# dedica_interface_board.net
KiCad netlist of a schematic drawn in EAGLE
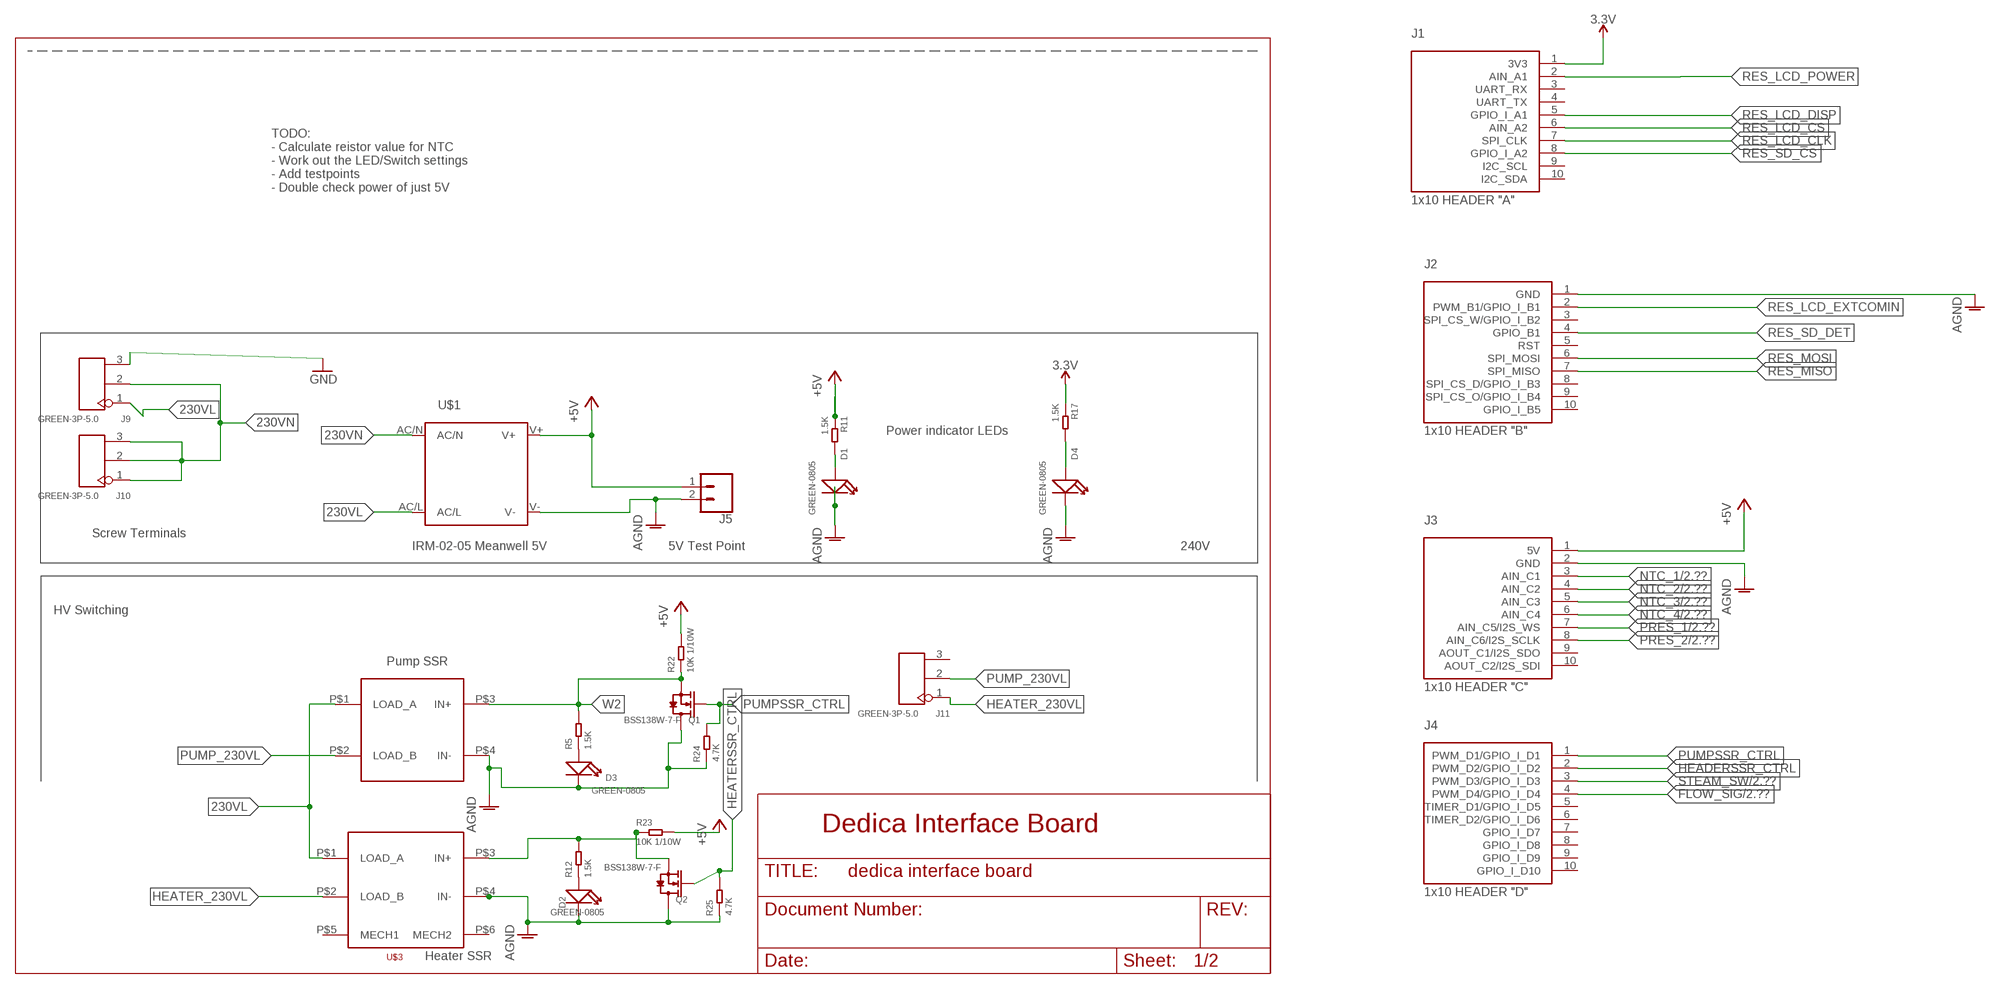
[diagram p0: schematic, sheet 1]
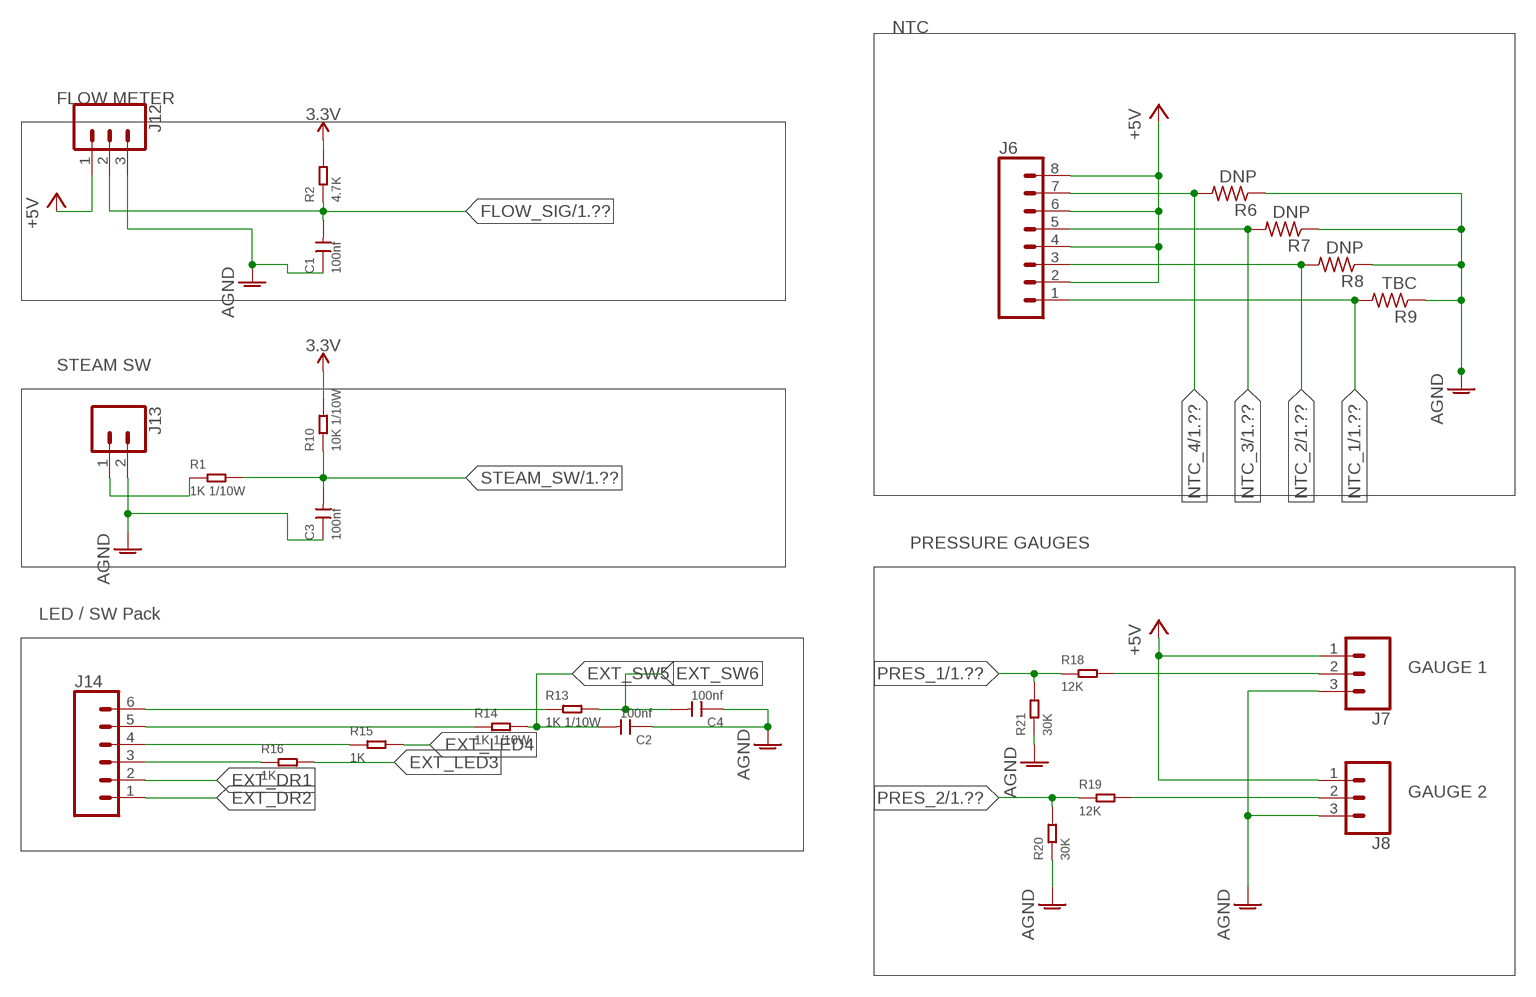
[diagram p1: schematic, sheet 2]

(export (version "E")
  (design (tool "Eeschema 10.0.6"))
  (components
    (comp (ref "C1")
      (value "100nf")
      (footprint "eagle-import:C0603")
      (fields (field (name "MPN") "CC0603KRX7R9BB104"))
      (libsource (lib "eagle-import") (part "CERAMIC-100NF-50V-10%-X7R(0603)"))
    )
    (comp (ref "C2")
      (value "100nf")
      (footprint "eagle-import:C0603")
      (fields (field (name "MPN") "CC0603KRX7R9BB104"))
      (libsource (lib "eagle-import") (part "CERAMIC-100NF-50V-10%-X7R(0603)"))
    )
    (comp (ref "C3")
      (value "100nf")
      (footprint "eagle-import:C0603")
      (fields (field (name "MPN") "CC0603KRX7R9BB104"))
      (libsource (lib "eagle-import") (part "CERAMIC-100NF-50V-10%-X7R(0603)"))
    )
    (comp (ref "C4")
      (value "100nf")
      (footprint "eagle-import:C0603")
      (fields (field (name "MPN") "CC0603KRX7R9BB104"))
      (libsource (lib "eagle-import") (part "CERAMIC-100NF-50V-10%-X7R(0603)"))
    )
    (comp (ref "J6")
      (value "CONN_08\"")
      (footprint "eagle-import:1X08")
      (libsource (lib "eagle-import") (part "CONN_08{dblquote}"))
    )
    (comp (ref "J7")
      (value "CONN_03")
      (footprint "eagle-import:1X03")
      (libsource (lib "eagle-import") (part "CONN_03"))
    )
    (comp (ref "J8")
      (value "CONN_03")
      (footprint "eagle-import:1X03")
      (libsource (lib "eagle-import") (part "CONN_03"))
    )
    (comp (ref "J12")
      (value "CONN_03")
      (footprint "eagle-import:1X03")
      (libsource (lib "eagle-import") (part "CONN_03"))
    )
    (comp (ref "J13")
      (value "CONN_02")
      (footprint "eagle-import:1X02")
      (libsource (lib "eagle-import") (part "CONN_02"))
    )
    (comp (ref "J14")
      (value "CONN_06LOCK")
      (footprint "eagle-import:1X06_LOCK")
      (libsource (lib "eagle-import") (part "CONN_06LOCK"))
    )
    (comp (ref "R1")
      (value "1K 1/10W")
      (footprint "eagle-import:R0603")
      (fields (field (name "MPN") "RC0603JR-071KL"))
      (libsource (lib "eagle-import") (part "SMD-RES-1K-5%-1/10W(0603)"))
    )
    (comp (ref "R2")
      (value "4.7K")
      (footprint "eagle-import:R0603")
      (fields (field (name "MPN") "RC0603JR-074K7L"))
      (libsource (lib "eagle-import") (part "SMD-RES-4.7K-5%-1/10W(0603)"))
    )
    (comp (ref "R6")
      (value "DNP")
      (footprint "eagle-import:R0603")
      (libsource (lib "eagle-import") (part "R-US_R0603"))
    )
    (comp (ref "R7")
      (value "DNP")
      (footprint "eagle-import:R0603")
      (libsource (lib "eagle-import") (part "R-US_R0603"))
    )
    (comp (ref "R8")
      (value "DNP")
      (footprint "eagle-import:R0603")
      (libsource (lib "eagle-import") (part "R-US_R0603"))
    )
    (comp (ref "R9")
      (value "TBC")
      (footprint "eagle-import:R0603")
      (libsource (lib "eagle-import") (part "R-US_R0603"))
    )
    (comp (ref "R10")
      (value "10K 1/10W")
      (footprint "eagle-import:R0603")
      (fields (field (name "MPN") "RC0603JR-0710KL"))
      (libsource (lib "eagle-import") (part "SMD-RES-10K-5%-1/10W(0603)"))
    )
    (comp (ref "R13")
      (value "1K 1/10W")
      (footprint "eagle-import:R0603")
      (fields (field (name "MPN") "RC0603JR-071KL"))
      (libsource (lib "eagle-import") (part "SMD-RES-1K-5%-1/10W(0603)"))
    )
    (comp (ref "R14")
      (value "1K 1/10W")
      (footprint "eagle-import:R0603")
      (fields (field (name "MPN") "RC0603JR-071KL"))
      (libsource (lib "eagle-import") (part "SMD-RES-1K-5%-1/10W(0603)"))
    )
    (comp (ref "R15")
      (value "1K")
      (footprint "eagle-import:R0805")
      (fields (field (name "MPN") "RC0805JR-071KL"))
      (libsource (lib "eagle-import") (part "SMD-RES-330R-5%-1/8W(0805)"))
    )
    (comp (ref "R16")
      (value "1K")
      (footprint "eagle-import:R0805")
      (fields (field (name "MPN") "RC0805JR-071KL"))
      (libsource (lib "eagle-import") (part "SMD-RES-330R-5%-1/8W(0805)"))
    )
    (comp (ref "R18")
      (value "12K")
      (footprint "eagle-import:R0603")
      (fields (field (name "MPN") "RC0603FR-0712KL"))
      (libsource (lib "eagle-import") (part "SMD-RES-12K-1%-1/10W(0603)"))
    )
    (comp (ref "R19")
      (value "12K")
      (footprint "eagle-import:R0603")
      (fields (field (name "MPN") "RC0603FR-0712KL"))
      (libsource (lib "eagle-import") (part "SMD-RES-12K-1%-1/10W(0603)"))
    )
    (comp (ref "R20")
      (value "30K")
      (footprint "eagle-import:R0603")
      (fields (field (name "MPN") "RC0603FR-0730KL"))
      (libsource (lib "eagle-import") (part "SMD-RES-30K-1%-1/10W(0603)"))
    )
    (comp (ref "R21")
      (value "30K")
      (footprint "eagle-import:R0603")
      (fields (field (name "MPN") "RC0603FR-0730KL"))
      (libsource (lib "eagle-import") (part "SMD-RES-30K-1%-1/10W(0603)"))
    )
    (comp (ref "D1")
      (value "GREEN-0805")
      (footprint "eagle-import:LED-0805")
      (fields (field (name "MPN") "17-215SYGC/S530-E2/TR8"))
      (libsource (lib "eagle-import") (part "SMD-LED-CLEAR-GREEN(0805)"))
    )
    (comp (ref "D2")
      (value "GREEN-0805")
      (footprint "eagle-import:LED-0805")
      (fields (field (name "MPN") "17-215SYGC/S530-E2/TR8"))
      (libsource (lib "eagle-import") (part "SMD-LED-CLEAR-GREEN(0805)"))
    )
    (comp (ref "D3")
      (value "GREEN-0805")
      (footprint "eagle-import:LED-0805")
      (fields (field (name "MPN") "17-215SYGC/S530-E2/TR8"))
      (libsource (lib "eagle-import") (part "SMD-LED-CLEAR-GREEN(0805)"))
    )
    (comp (ref "D4")
      (value "GREEN-0805")
      (footprint "eagle-import:LED-0805")
      (fields (field (name "MPN") "17-215SYGC/S530-E2/TR8"))
      (libsource (lib "eagle-import") (part "SMD-LED-CLEAR-GREEN(0805)"))
    )
    (comp (ref "J1")
      (value "1x10 HEADER \"A\"")
      (footprint "eagle-import:1X10")
      (libsource (lib "eagle-import") (part "HEADER-1X10-J1"))
    )
    (comp (ref "J2")
      (value "1x10 HEADER \"B\"")
      (footprint "eagle-import:1X10")
      (libsource (lib "eagle-import") (part "HEADER-1X10-J2"))
    )
    (comp (ref "J3")
      (value "1x10 HEADER \"C\"")
      (footprint "eagle-import:1X10")
      (libsource (lib "eagle-import") (part "HEADER-1X10-J3"))
    )
    (comp (ref "J4")
      (value "1x10 HEADER \"D\"")
      (footprint "eagle-import:1X10")
      (libsource (lib "eagle-import") (part "HEADER-1X10-J4"))
    )
    (comp (ref "J5")
      (value "CONN_02")
      (footprint "eagle-import:1X02")
      (libsource (lib "eagle-import") (part "CONN_02"))
    )
    (comp (ref "J9")
      (value "GREEN-3P-5.0")
      (footprint "eagle-import:H3-5.0-15.5X8.0MM")
      (libsource (lib "eagle-import") (part "SCREW-TERMINAL-GREEN(3P-5.0)"))
    )
    (comp (ref "J10")
      (value "GREEN-3P-5.0")
      (footprint "eagle-import:H3-5.0-15.5X8.0MM")
      (libsource (lib "eagle-import") (part "SCREW-TERMINAL-GREEN(3P-5.0)"))
    )
    (comp (ref "J11")
      (value "GREEN-3P-5.0")
      (footprint "eagle-import:H3-5.0-15.5X8.0MM")
      (libsource (lib "eagle-import") (part "SCREW-TERMINAL-GREEN(3P-5.0)"))
    )
    (comp (ref "Q1")
      (value "BSS138W-7-F")
      (footprint "eagle-import:SOT-23")
      (libsource (lib "eagle-import") (part "SMD-MOSFET-N-CH-50V-200MA-BSS138W-7-F(SOT-23)"))
    )
    (comp (ref "Q2")
      (value "BSS138W-7-F")
      (footprint "eagle-import:SOT-23")
      (libsource (lib "eagle-import") (part "SMD-MOSFET-N-CH-50V-200MA-BSS138W-7-F(SOT-23)"))
    )
    (comp (ref "R5")
      (value "1.5K")
      (footprint "eagle-import:R0603")
      (fields (field (name "MPN") "RC0603FR-071K5L"))
      (libsource (lib "eagle-import") (part "SMD-RES-330R-5%-1/10W(0603)"))
    )
    (comp (ref "R11")
      (value "1.5K")
      (footprint "eagle-import:R0603")
      (fields (field (name "MPN") "RC0603FR-071K5L"))
      (libsource (lib "eagle-import") (part "SMD-RES-150R-5%-1/10W(0603)"))
    )
    (comp (ref "R12")
      (value "1.5K")
      (footprint "eagle-import:R0603")
      (fields (field (name "MPN") "RC0603FR-071K5L"))
      (libsource (lib "eagle-import") (part "SMD-RES-330R-5%-1/10W(0603)"))
    )
    (comp (ref "R17")
      (value "1.5K")
      (footprint "eagle-import:R0603")
      (fields (field (name "MPN") "RC0603FR-071K5L"))
      (libsource (lib "eagle-import") (part "SMD-RES-150R-5%-1/10W(0603)"))
    )
    (comp (ref "R22")
      (value "10K 1/10W")
      (footprint "eagle-import:R0603")
      (fields (field (name "MPN") "RC0603JR-0710KL"))
      (libsource (lib "eagle-import") (part "SMD-RES-10K-5%-1/10W(0603)"))
    )
    (comp (ref "R23")
      (value "10K 1/10W")
      (footprint "eagle-import:R0603")
      (fields (field (name "MPN") "RC0603JR-0710KL"))
      (libsource (lib "eagle-import") (part "SMD-RES-10K-5%-1/10W(0603)"))
    )
    (comp (ref "R24")
      (value "4.7K")
      (footprint "eagle-import:R0603")
      (fields (field (name "MPN") "RC0603JR-074K7L"))
      (libsource (lib "eagle-import") (part "SMD-RES-4.7K-5%-1/10W(0603)"))
    )
    (comp (ref "R25")
      (value "4.7K")
      (footprint "eagle-import:R0603")
      (fields (field (name "MPN") "RC0603JR-074K7L"))
      (libsource (lib "eagle-import") (part "SMD-RES-4.7K-5%-1/10W(0603)"))
    )
    (comp (ref "U$1")
      (value "IRM_01/02IRM_01/02")
      (footprint "eagle-import:IRM_01_02")
      (libsource (lib "eagle-import") (part "IRM_01/02IRM_01/02"))
    )
    (comp (ref "U$2")
      (value "AQ3A2-ZT4/32VDC")
      (footprint "eagle-import:AQ3A2-ZT4_32VDC")
      (libsource (lib "eagle-import") (part "AQ3A2-ZT4/32VDC"))
    )
    (comp (ref "U$3")
      (value "AQ10A2-ZT4/32VDC")
      (footprint "eagle-import:AQ10A2-ZT4_32VDC")
      (libsource (lib "eagle-import") (part "AQ10A2-ZT4/32VDC"))
    )
  )
  (nets
    (net (code "1") (name "+5V") (class "Default")
      (node (ref "J12") (pin "1") (pinfunction "1_1") (pintype "passive"))
      (node (ref "J3") (pin "1") (pinfunction "5V_1") (pintype "bidirectional"))
      (node (ref "J5") (pin "1") (pinfunction "1_1") (pintype "passive"))
      (node (ref "J6") (pin "2") (pinfunction "2_2") (pintype "passive"))
      (node (ref "J6") (pin "4") (pinfunction "4_4") (pintype "passive"))
      (node (ref "J6") (pin "6") (pinfunction "6_6") (pintype "passive"))
      (node (ref "J6") (pin "8") (pinfunction "8_8") (pintype "passive"))
      (node (ref "J7") (pin "1") (pinfunction "1_1") (pintype "passive"))
      (node (ref "J8") (pin "1") (pinfunction "1_1") (pintype "passive"))
      (node (ref "R11") (pin "1") (pinfunction "1_1") (pintype "passive"))
      (node (ref "R22") (pin "2") (pinfunction "2_2") (pintype "passive"))
      (node (ref "R23") (pin "2") (pinfunction "2_2") (pintype "passive"))
      (node (ref "U$1") (pin "V+") (pinfunction "V+_V+") (pintype "output"))
    )
    (net (code "2") (name "3.3V") (class "Default")
      (node (ref "J1") (pin "1") (pinfunction "3V3_1") (pintype "bidirectional"))
      (node (ref "R10") (pin "2") (pinfunction "2_2") (pintype "passive"))
      (node (ref "R17") (pin "1") (pinfunction "1_1") (pintype "passive"))
      (node (ref "R2") (pin "2") (pinfunction "2_2") (pintype "passive"))
    )
    (net (code "3") (name "230VL") (class "Default")
      (node (ref "J9") (pin "1") (pinfunction "P$1_1") (pintype "bidirectional"))
      (node (ref "U$1") (pin "AC/L") (pinfunction "AC/L_AC/L") (pintype "input"))
      (node (ref "U$2") (pin "P$1") (pinfunction "LOAD_A_P$1") (pintype "bidirectional"))
      (node (ref "U$3") (pin "P$1") (pinfunction "LOAD_A_P$1") (pintype "bidirectional"))
    )
    (net (code "4") (name "230VN") (class "Default")
      (node (ref "J10") (pin "1") (pinfunction "P$1_1") (pintype "bidirectional"))
      (node (ref "J10") (pin "2") (pinfunction "P$2_2") (pintype "bidirectional"))
      (node (ref "J10") (pin "3") (pinfunction "P$3_3") (pintype "bidirectional"))
      (node (ref "J9") (pin "2") (pinfunction "P$2_2") (pintype "bidirectional"))
      (node (ref "U$1") (pin "AC/N") (pinfunction "AC/N_AC/N") (pintype "input"))
    )
    (net (code "5") (name "AGND") (class "Default")
      (node (ref "C1") (pin "1") (pinfunction "1_1") (pintype "passive"))
      (node (ref "C2") (pin "1") (pinfunction "1_1") (pintype "passive"))
      (node (ref "C3") (pin "1") (pinfunction "1_1") (pintype "passive"))
      (node (ref "C4") (pin "1") (pinfunction "1_1") (pintype "passive"))
      (node (ref "D1") (pin "-") (pinfunction "-_-") (pintype "passive"))
      (node (ref "D2") (pin "-") (pinfunction "-_-") (pintype "passive"))
      (node (ref "D3") (pin "-") (pinfunction "-_-") (pintype "passive"))
      (node (ref "D4") (pin "-") (pinfunction "-_-") (pintype "passive"))
      (node (ref "J12") (pin "3") (pinfunction "3_3") (pintype "passive"))
      (node (ref "J13") (pin "2") (pinfunction "2_2") (pintype "passive"))
      (node (ref "J2") (pin "1") (pinfunction "GND_1") (pintype "bidirectional"))
      (node (ref "J3") (pin "2") (pinfunction "GND_2") (pintype "bidirectional"))
      (node (ref "J5") (pin "2") (pinfunction "2_2") (pintype "passive"))
      (node (ref "J7") (pin "3") (pinfunction "3_3") (pintype "passive"))
      (node (ref "J8") (pin "3") (pinfunction "3_3") (pintype "passive"))
      (node (ref "Q1") (pin "3") (pinfunction "D_3") (pintype "passive"))
      (node (ref "Q2") (pin "3") (pinfunction "D_3") (pintype "passive"))
      (node (ref "R20") (pin "1") (pinfunction "1_1") (pintype "passive"))
      (node (ref "R21") (pin "1") (pinfunction "1_1") (pintype "passive"))
      (node (ref "R24") (pin "1") (pinfunction "1_1") (pintype "passive"))
      (node (ref "R25") (pin "1") (pinfunction "1_1") (pintype "passive"))
      (node (ref "R6") (pin "1") (pinfunction "1_1") (pintype "passive"))
      (node (ref "R7") (pin "1") (pinfunction "1_1") (pintype "passive"))
      (node (ref "R8") (pin "1") (pinfunction "1_1") (pintype "passive"))
      (node (ref "R9") (pin "1") (pinfunction "1_1") (pintype "passive"))
      (node (ref "U$1") (pin "V-") (pinfunction "V-_V-") (pintype "output"))
      (node (ref "U$2") (pin "P$4") (pinfunction "IN-_P$4") (pintype "bidirectional"))
      (node (ref "U$3") (pin "P$4") (pinfunction "IN-_P$4") (pintype "bidirectional"))
    )
    (net (code "6") (name "EXT_DR1") (class "Default")
      (node (ref "J14") (pin "2") (pinfunction "2_2") (pintype "passive"))
    )
    (net (code "7") (name "EXT_DR2") (class "Default")
      (node (ref "J14") (pin "1") (pinfunction "1_1") (pintype "passive"))
    )
    (net (code "8") (name "EXT_LED3") (class "Default")
      (node (ref "R16") (pin "2") (pinfunction "2_2") (pintype "passive"))
    )
    (net (code "9") (name "EXT_LED4") (class "Default")
      (node (ref "R15") (pin "2") (pinfunction "2_2") (pintype "passive"))
    )
    (net (code "10") (name "EXT_SW5") (class "Default")
      (node (ref "C2") (pin "2") (pinfunction "2_2") (pintype "passive"))
      (node (ref "R14") (pin "2") (pinfunction "2_2") (pintype "passive"))
    )
    (net (code "11") (name "EXT_SW6") (class "Default")
      (node (ref "C4") (pin "2") (pinfunction "2_2") (pintype "passive"))
      (node (ref "R13") (pin "2") (pinfunction "2_2") (pintype "passive"))
    )
    (net (code "12") (name "FLOW_SIG") (class "Default")
      (node (ref "C1") (pin "2") (pinfunction "2_2") (pintype "passive"))
      (node (ref "J12") (pin "2") (pinfunction "2_2") (pintype "passive"))
      (node (ref "J4") (pin "4") (pinfunction "PWM_D4/GPIO_I_D4_4") (pintype "bidirectional"))
      (node (ref "R2") (pin "1") (pinfunction "1_1") (pintype "passive"))
    )
    (net (code "13") (name "GND") (class "Default")
      (node (ref "J9") (pin "3") (pinfunction "P$3_3") (pintype "bidirectional"))
    )
    (net (code "14") (name "HEADERSSR_CTRL") (class "Default")
      (node (ref "J4") (pin "2") (pinfunction "PWM_D2/GPIO_I_D2_2") (pintype "bidirectional"))
    )
    (net (code "15") (name "HEATERSSR_CTRL") (class "Default")
      (node (ref "Q2") (pin "1") (pinfunction "G_1") (pintype "passive"))
      (node (ref "R25") (pin "2") (pinfunction "2_2") (pintype "passive"))
    )
    (net (code "16") (name "HEATER_230VL") (class "Default")
      (node (ref "J11") (pin "1") (pinfunction "P$1_1") (pintype "bidirectional"))
      (node (ref "U$3") (pin "P$2") (pinfunction "LOAD_B_P$2") (pintype "bidirectional"))
    )
    (net (code "17") (name "NTC_1") (class "Default")
      (node (ref "J3") (pin "3") (pinfunction "AIN_C1_3") (pintype "bidirectional"))
      (node (ref "J6") (pin "1") (pinfunction "1_1") (pintype "passive"))
      (node (ref "R9") (pin "2") (pinfunction "2_2") (pintype "passive"))
    )
    (net (code "18") (name "NTC_2") (class "Default")
      (node (ref "J3") (pin "4") (pinfunction "AIN_C2_4") (pintype "bidirectional"))
      (node (ref "J6") (pin "3") (pinfunction "3_3") (pintype "passive"))
      (node (ref "R8") (pin "2") (pinfunction "2_2") (pintype "passive"))
    )
    (net (code "19") (name "NTC_3") (class "Default")
      (node (ref "J3") (pin "5") (pinfunction "AIN_C3_5") (pintype "bidirectional"))
      (node (ref "J6") (pin "5") (pinfunction "5_5") (pintype "passive"))
      (node (ref "R7") (pin "2") (pinfunction "2_2") (pintype "passive"))
    )
    (net (code "20") (name "NTC_4") (class "Default")
      (node (ref "J3") (pin "6") (pinfunction "AIN_C4_6") (pintype "bidirectional"))
      (node (ref "J6") (pin "7") (pinfunction "7_7") (pintype "passive"))
      (node (ref "R6") (pin "2") (pinfunction "2_2") (pintype "passive"))
    )
    (net (code "21") (name "Net-(D1-Pad+)") (class "Default")
      (node (ref "D1") (pin "+") (pinfunction "+_+") (pintype "passive"))
      (node (ref "R11") (pin "2") (pinfunction "2_2") (pintype "passive"))
    )
    (net (code "22") (name "Net-(D2-Pad+)") (class "Default")
      (node (ref "D2") (pin "+") (pinfunction "+_+") (pintype "passive"))
      (node (ref "R12") (pin "1") (pinfunction "1_1") (pintype "passive"))
    )
    (net (code "23") (name "Net-(D3-Pad+)") (class "Default")
      (node (ref "D3") (pin "+") (pinfunction "+_+") (pintype "passive"))
      (node (ref "R5") (pin "1") (pinfunction "1_1") (pintype "passive"))
    )
    (net (code "24") (name "Net-(D4-Pad+)") (class "Default")
      (node (ref "D4") (pin "+") (pinfunction "+_+") (pintype "passive"))
      (node (ref "R17") (pin "2") (pinfunction "2_2") (pintype "passive"))
    )
    (net (code "25") (name "Net-(J7-Pad2)") (class "Default")
      (node (ref "J7") (pin "2") (pinfunction "2_2") (pintype "passive"))
      (node (ref "R18") (pin "2") (pinfunction "2_2") (pintype "passive"))
    )
    (net (code "26") (name "Net-(J8-Pad2)") (class "Default")
      (node (ref "J8") (pin "2") (pinfunction "2_2") (pintype "passive"))
      (node (ref "R19") (pin "2") (pinfunction "2_2") (pintype "passive"))
    )
    (net (code "27") (name "Net-(J13-Pad1)") (class "Default")
      (node (ref "J13") (pin "1") (pinfunction "1_1") (pintype "passive"))
      (node (ref "R1") (pin "1") (pinfunction "1_1") (pintype "passive"))
    )
    (net (code "28") (name "Net-(J14-Pad3)") (class "Default")
      (node (ref "J14") (pin "3") (pinfunction "3_3") (pintype "passive"))
      (node (ref "R16") (pin "1") (pinfunction "1_1") (pintype "passive"))
    )
    (net (code "29") (name "Net-(J14-Pad4)") (class "Default")
      (node (ref "J14") (pin "4") (pinfunction "4_4") (pintype "passive"))
      (node (ref "R15") (pin "1") (pinfunction "1_1") (pintype "passive"))
    )
    (net (code "30") (name "Net-(J14-Pad5)") (class "Default")
      (node (ref "J14") (pin "5") (pinfunction "5_5") (pintype "passive"))
      (node (ref "R14") (pin "1") (pinfunction "1_1") (pintype "passive"))
    )
    (net (code "31") (name "Net-(J14-Pad6)") (class "Default")
      (node (ref "J14") (pin "6") (pinfunction "6_6") (pintype "passive"))
      (node (ref "R13") (pin "1") (pinfunction "1_1") (pintype "passive"))
    )
    (net (code "32") (name "Net-(Q2-S)") (class "Default")
      (node (ref "Q2") (pin "2") (pinfunction "S_2") (pintype "passive"))
      (node (ref "R12") (pin "2") (pinfunction "2_2") (pintype "passive"))
      (node (ref "R23") (pin "1") (pinfunction "1_1") (pintype "passive"))
      (node (ref "U$3") (pin "P$3") (pinfunction "IN+_P$3") (pintype "bidirectional"))
    )
    (net (code "33") (name "PRES_1") (class "Default")
      (node (ref "J3") (pin "7") (pinfunction "AIN_C5/I2S_WS_7") (pintype "bidirectional"))
      (node (ref "R18") (pin "1") (pinfunction "1_1") (pintype "passive"))
      (node (ref "R21") (pin "2") (pinfunction "2_2") (pintype "passive"))
    )
    (net (code "34") (name "PRES_2") (class "Default")
      (node (ref "J3") (pin "8") (pinfunction "AIN_C6/I2S_SCLK_8") (pintype "bidirectional"))
      (node (ref "R19") (pin "1") (pinfunction "1_1") (pintype "passive"))
      (node (ref "R20") (pin "2") (pinfunction "2_2") (pintype "passive"))
    )
    (net (code "35") (name "PUMPSSR_CTRL") (class "Default")
      (node (ref "J4") (pin "1") (pinfunction "PWM_D1/GPIO_I_D1_1") (pintype "bidirectional"))
      (node (ref "Q1") (pin "1") (pinfunction "G_1") (pintype "passive"))
      (node (ref "R24") (pin "2") (pinfunction "2_2") (pintype "passive"))
    )
    (net (code "36") (name "PUMP_230VL") (class "Default")
      (node (ref "J11") (pin "2") (pinfunction "P$2_2") (pintype "bidirectional"))
      (node (ref "U$2") (pin "P$2") (pinfunction "LOAD_B_P$2") (pintype "bidirectional"))
    )
    (net (code "37") (name "RES_LCD_CLK") (class "Default")
      (node (ref "J1") (pin "7") (pinfunction "SPI_CLK_7") (pintype "bidirectional"))
    )
    (net (code "38") (name "RES_LCD_CS") (class "Default")
      (node (ref "J1") (pin "6") (pinfunction "AIN_A2_6") (pintype "bidirectional"))
    )
    (net (code "39") (name "RES_LCD_DISP") (class "Default")
      (node (ref "J1") (pin "5") (pinfunction "GPIO_I_A1_5") (pintype "bidirectional"))
    )
    (net (code "40") (name "RES_LCD_EXTCOMIN") (class "Default")
      (node (ref "J2") (pin "2") (pinfunction "PWM_B1/GPIO_I_B1_2") (pintype "bidirectional"))
    )
    (net (code "41") (name "RES_LCD_POWER") (class "Default")
      (node (ref "J1") (pin "2") (pinfunction "AIN_A1_2") (pintype "bidirectional"))
    )
    (net (code "42") (name "RES_MISO") (class "Default")
      (node (ref "J2") (pin "7") (pinfunction "SPI_MISO_7") (pintype "bidirectional"))
    )
    (net (code "43") (name "RES_MOSI") (class "Default")
      (node (ref "J2") (pin "6") (pinfunction "SPI_MOSI_6") (pintype "bidirectional"))
    )
    (net (code "44") (name "RES_SD_CS") (class "Default")
      (node (ref "J1") (pin "8") (pinfunction "GPIO_I_A2_8") (pintype "bidirectional"))
    )
    (net (code "45") (name "RES_SD_DET") (class "Default")
      (node (ref "J2") (pin "4") (pinfunction "GPIO_B1_4") (pintype "bidirectional"))
    )
    (net (code "46") (name "STEAM_SW") (class "Default")
      (node (ref "C3") (pin "2") (pinfunction "2_2") (pintype "passive"))
      (node (ref "J4") (pin "3") (pinfunction "PWM_D3/GPIO_I_D3_3") (pintype "bidirectional"))
      (node (ref "R1") (pin "2") (pinfunction "2_2") (pintype "passive"))
      (node (ref "R10") (pin "1") (pinfunction "1_1") (pintype "passive"))
    )
    (net (code "47") (name "W2") (class "Default")
      (node (ref "Q1") (pin "2") (pinfunction "S_2") (pintype "passive"))
      (node (ref "R22") (pin "1") (pinfunction "1_1") (pintype "passive"))
      (node (ref "R5") (pin "2") (pinfunction "2_2") (pintype "passive"))
      (node (ref "U$2") (pin "P$3") (pinfunction "IN+_P$3") (pintype "bidirectional"))
    )
    (net (code "48") (name "unconnected-(J1-I2C_SCL-Pad9)") (class "Default")
      (node (ref "J1") (pin "9") (pinfunction "I2C_SCL_9") (pintype "bidirectional"))
    )
    (net (code "49") (name "unconnected-(J1-I2C_SDA-Pad10)") (class "Default")
      (node (ref "J1") (pin "10") (pinfunction "I2C_SDA_10") (pintype "bidirectional"))
    )
    (net (code "50") (name "unconnected-(J1-UART_RX-Pad3)") (class "Default")
      (node (ref "J1") (pin "3") (pinfunction "UART_RX_3") (pintype "bidirectional"))
    )
    (net (code "51") (name "unconnected-(J1-UART_TX-Pad4)") (class "Default")
      (node (ref "J1") (pin "4") (pinfunction "UART_TX_4") (pintype "bidirectional"))
    )
    (net (code "52") (name "unconnected-(J2-GPIO_I_B5-Pad10)") (class "Default")
      (node (ref "J2") (pin "10") (pinfunction "GPIO_I_B5_10") (pintype "bidirectional"))
    )
    (net (code "53") (name "unconnected-(J2-RST-Pad5)") (class "Default")
      (node (ref "J2") (pin "5") (pinfunction "RST_5") (pintype "bidirectional"))
    )
    (net (code "54") (name "unconnected-(J2-SPI_CS_D{slash}GPIO_I_B3-Pad8)") (class "Default")
      (node (ref "J2") (pin "8") (pinfunction "SPI_CS_D/GPIO_I_B3_8") (pintype "bidirectional"))
    )
    (net (code "55") (name "unconnected-(J2-SPI_CS_O{slash}GPIO_I_B4-Pad9)") (class "Default")
      (node (ref "J2") (pin "9") (pinfunction "SPI_CS_O/GPIO_I_B4_9") (pintype "bidirectional"))
    )
    (net (code "56") (name "unconnected-(J2-SPI_CS_W{slash}GPIO_I_B2-Pad3)") (class "Default")
      (node (ref "J2") (pin "3") (pinfunction "SPI_CS_W/GPIO_I_B2_3") (pintype "bidirectional"))
    )
    (net (code "57") (name "unconnected-(J3-AOUT_C1{slash}I2S_SDO-Pad9)") (class "Default")
      (node (ref "J3") (pin "9") (pinfunction "AOUT_C1/I2S_SDO_9") (pintype "bidirectional"))
    )
    (net (code "58") (name "unconnected-(J3-AOUT_C2{slash}I2S_SDI-Pad10)") (class "Default")
      (node (ref "J3") (pin "10") (pinfunction "AOUT_C2/I2S_SDI_10") (pintype "bidirectional"))
    )
    (net (code "59") (name "unconnected-(J4-GPIO_I_D7-Pad7)") (class "Default")
      (node (ref "J4") (pin "7") (pinfunction "GPIO_I_D7_7") (pintype "bidirectional"))
    )
    (net (code "60") (name "unconnected-(J4-GPIO_I_D8-Pad8)") (class "Default")
      (node (ref "J4") (pin "8") (pinfunction "GPIO_I_D8_8") (pintype "bidirectional"))
    )
    (net (code "61") (name "unconnected-(J4-GPIO_I_D9-Pad9)") (class "Default")
      (node (ref "J4") (pin "9") (pinfunction "GPIO_I_D9_9") (pintype "bidirectional"))
    )
    (net (code "62") (name "unconnected-(J4-GPIO_I_D10-Pad10)") (class "Default")
      (node (ref "J4") (pin "10") (pinfunction "GPIO_I_D10_10") (pintype "bidirectional"))
    )
    (net (code "63") (name "unconnected-(J4-TIMER_D1{slash}GPIO_I_D5-Pad5)") (class "Default")
      (node (ref "J4") (pin "5") (pinfunction "TIMER_D1/GPIO_I_D5_5") (pintype "bidirectional"))
    )
    (net (code "64") (name "unconnected-(J4-TIMER_D2{slash}GPIO_I_D6-Pad6)") (class "Default")
      (node (ref "J4") (pin "6") (pinfunction "TIMER_D2/GPIO_I_D6_6") (pintype "bidirectional"))
    )
    (net (code "65") (name "unconnected-(J11-P$3-Pad3)") (class "Default")
      (node (ref "J11") (pin "3") (pinfunction "P$3_3") (pintype "bidirectional"))
    )
    (net (code "66") (name "unconnected-(U$3-MECH1-PadP$5)") (class "Default")
      (node (ref "U$3") (pin "P$5") (pinfunction "MECH1_P$5") (pintype "bidirectional"))
    )
    (net (code "67") (name "unconnected-(U$3-MECH2-PadP$6)") (class "Default")
      (node (ref "U$3") (pin "P$6") (pinfunction "MECH2_P$6") (pintype "bidirectional"))
    )
  )
)
